# interface-board.net
KiCad netlist of a schematic drawn in Altium Designer
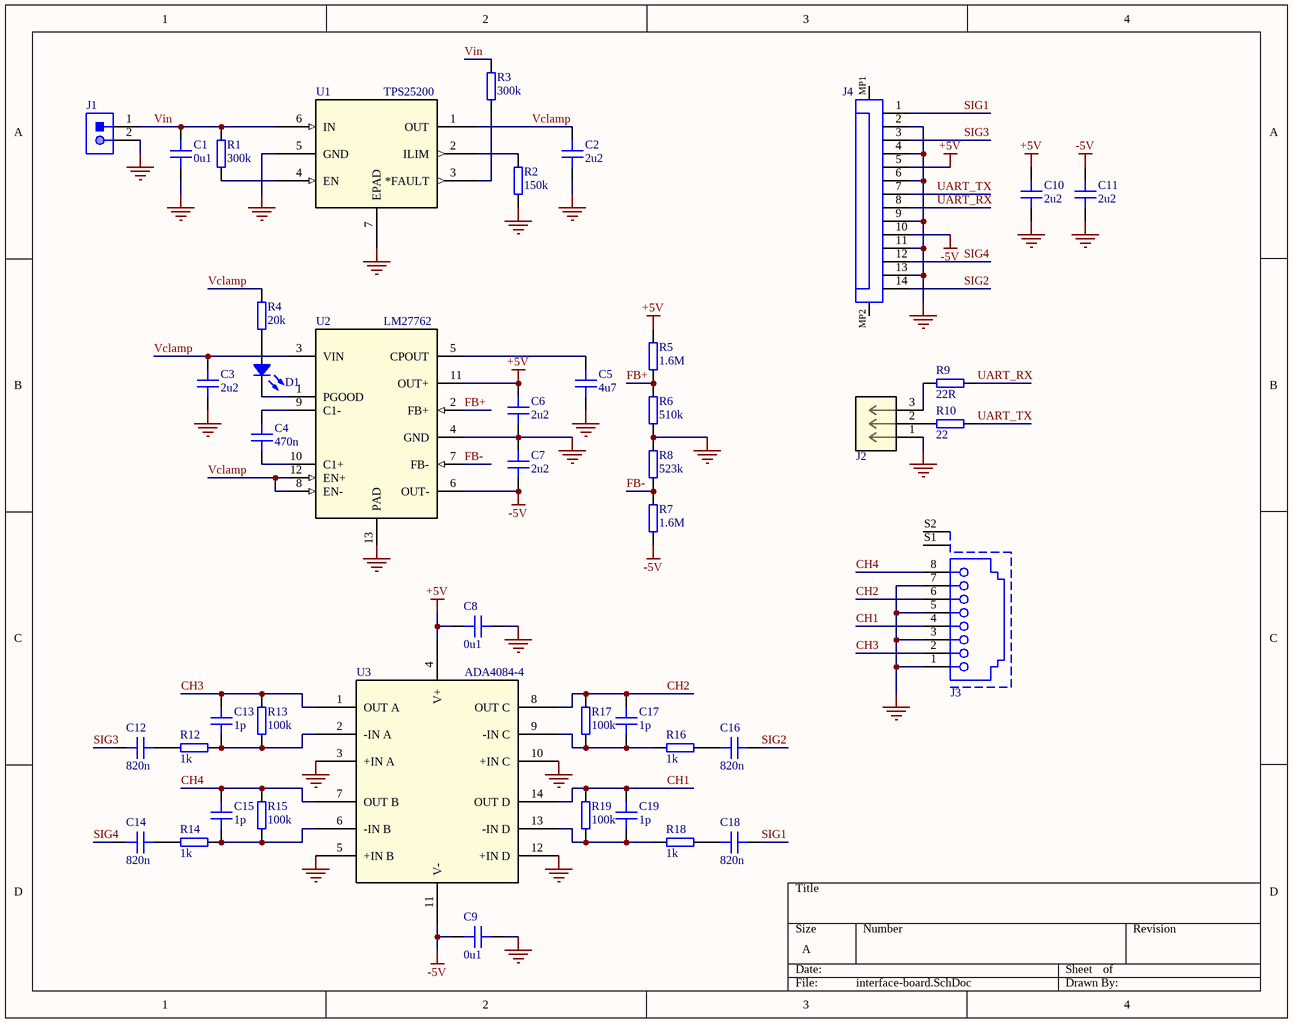
[diagram p0: interface-board.SchDoc]

(export (version "E")
  (design (tool "Eeschema 10.0.6"))
  (components
    (comp (ref "C1")
      (value "0u1")
      (footprint "CAP_0402")
      (description "Capacitor SMD 0402")
      (fields (field (name "VOLTAGE") "50V"))
      (libsource (lib "symbols") (part "CAP_0402"))
    )
    (comp (ref "C2")
      (value "2u2")
      (footprint "CAP_0402")
      (description "Capacitor SMD 0402")
      (fields (field (name "VOLTAGE") "50V"))
      (libsource (lib "symbols") (part "CAP_0402"))
    )
    (comp (ref "C3")
      (value "2u2")
      (footprint "CAP_0402")
      (description "Capacitor SMD 0402")
      (fields (field (name "VOLTAGE") "50V"))
      (libsource (lib "symbols") (part "CAP_0402"))
    )
    (comp (ref "C4")
      (value "470n")
      (footprint "CAP_0402")
      (description "Capacitor SMD 0402")
      (fields (field (name "VOLTAGE") "50V"))
      (libsource (lib "symbols") (part "CAP_0402"))
    )
    (comp (ref "C5")
      (value "4u7")
      (footprint "CAP_0402")
      (description "Capacitor SMD 0402")
      (fields (field (name "VOLTAGE") "50V"))
      (libsource (lib "symbols") (part "CAP_0402"))
    )
    (comp (ref "C6")
      (value "2u2")
      (footprint "CAP_0402")
      (description "Capacitor SMD 0402")
      (fields (field (name "VOLTAGE") "50V"))
      (libsource (lib "symbols") (part "CAP_0402"))
    )
    (comp (ref "C7")
      (value "2u2")
      (footprint "CAP_0402")
      (description "Capacitor SMD 0402")
      (fields (field (name "VOLTAGE") "50V"))
      (libsource (lib "symbols") (part "CAP_0402"))
    )
    (comp (ref "C8")
      (value "0u1")
      (footprint "CAP_0402")
      (description "Capacitor SMD 0402")
      (fields (field (name "VOLTAGE") "50V"))
      (libsource (lib "symbols") (part "CAP_0402"))
    )
    (comp (ref "C9")
      (value "0u1")
      (footprint "CAP_0402")
      (description "Capacitor SMD 0402")
      (fields (field (name "VOLTAGE") "50V"))
      (libsource (lib "symbols") (part "CAP_0402"))
    )
    (comp (ref "C10")
      (value "2u2")
      (footprint "CAP_0402")
      (description "Capacitor SMD 0402")
      (fields (field (name "VOLTAGE") "50V"))
      (libsource (lib "symbols") (part "CAP_0402"))
    )
    (comp (ref "C11")
      (value "2u2")
      (footprint "CAP_0402")
      (description "Capacitor SMD 0402")
      (fields (field (name "VOLTAGE") "50V"))
      (libsource (lib "symbols") (part "CAP_0402"))
    )
    (comp (ref "C12")
      (value "820n")
      (footprint "CAP_0402")
      (description "Capacitor SMD 0402")
      (fields (field (name "VOLTAGE") "50V"))
      (libsource (lib "symbols") (part "CAP_0402"))
    )
    (comp (ref "C13")
      (value "1p")
      (footprint "CAP_0402")
      (description "Capacitor SMD 0402")
      (fields (field (name "VOLTAGE") "50V"))
      (libsource (lib "symbols") (part "CAP_0402"))
    )
    (comp (ref "C14")
      (value "820n")
      (footprint "CAP_0402")
      (description "Capacitor SMD 0402")
      (fields (field (name "VOLTAGE") "50V"))
      (libsource (lib "symbols") (part "CAP_0402"))
    )
    (comp (ref "C15")
      (value "1p")
      (footprint "CAP_0402")
      (description "Capacitor SMD 0402")
      (fields (field (name "VOLTAGE") "50V"))
      (libsource (lib "symbols") (part "CAP_0402"))
    )
    (comp (ref "C16")
      (value "820n")
      (footprint "CAP_0402")
      (description "Capacitor SMD 0402")
      (fields (field (name "VOLTAGE") "50V"))
      (libsource (lib "symbols") (part "CAP_0402"))
    )
    (comp (ref "C17")
      (value "1p")
      (footprint "CAP_0402")
      (description "Capacitor SMD 0402")
      (fields (field (name "VOLTAGE") "50V"))
      (libsource (lib "symbols") (part "CAP_0402"))
    )
    (comp (ref "C18")
      (value "820n")
      (footprint "CAP_0402")
      (description "Capacitor SMD 0402")
      (fields (field (name "VOLTAGE") "50V"))
      (libsource (lib "symbols") (part "CAP_0402"))
    )
    (comp (ref "C19")
      (value "1p")
      (footprint "CAP_0402")
      (description "Capacitor SMD 0402")
      (fields (field (name "VOLTAGE") "50V"))
      (libsource (lib "symbols") (part "CAP_0402"))
    )
    (comp (ref "D1")
      (value "LED_0402")
      (footprint "LED_0402")
      (description "LED SMD 0402")
      (libsource (lib "symbols") (part "LED_0402"))
    )
    (comp (ref "J1")
      (value "XH_2.54_2P")
      (footprint "XH_2.54_2P")
      (description "XH, pitch 2.54 mm, 2 pisition")
      (libsource (lib "symbols") (part "XH_2.54_2P"))
    )
    (comp (ref "J2")
      (value "PH_2.0_3P")
      (footprint "PH_2.0_3P")
      (description "PH, pitch 2.0 mm, 3 pisition")
      (libsource (lib "symbols") (part "PH_2.0_3P"))
    )
    (comp (ref "J3") (value "RJ45") (footprint "RJ45") (libsource (lib "symbols") (part "RJ45")))
    (comp (ref "J4")
      (value "FPC_0.5_14P")
      (footprint "FPC_0.5_14P")
      (description "FPC, Horizontal, pitch 0.5 mm, 14 pins")
      (libsource (lib "symbols") (part "FPC_0.5_14P"))
    )
    (comp (ref "R1")
      (value "300k")
      (footprint "RES_0402")
      (description "Resistor SMD 0402")
      (libsource (lib "symbols") (part "RES_0402"))
    )
    (comp (ref "R2")
      (value "150k")
      (footprint "RES_0402")
      (description "Resistor SMD 0402")
      (libsource (lib "symbols") (part "RES_0402"))
    )
    (comp (ref "R3")
      (value "300k")
      (footprint "RES_0402")
      (description "Resistor SMD 0402")
      (libsource (lib "symbols") (part "RES_0402"))
    )
    (comp (ref "R4")
      (value "20k")
      (footprint "RES_0402")
      (description "Resistor SMD 0402")
      (libsource (lib "symbols") (part "RES_0402"))
    )
    (comp (ref "R5")
      (value "1.6M")
      (footprint "RES_0402")
      (description "Resistor SMD 0402")
      (libsource (lib "symbols") (part "RES_0402"))
    )
    (comp (ref "R6")
      (value "510k")
      (footprint "RES_0402")
      (description "Resistor SMD 0402")
      (libsource (lib "symbols") (part "RES_0402"))
    )
    (comp (ref "R7")
      (value "1.6M")
      (footprint "RES_0402")
      (description "Resistor SMD 0402")
      (libsource (lib "symbols") (part "RES_0402"))
    )
    (comp (ref "R8")
      (value "523k")
      (footprint "RES_0402")
      (description "Resistor SMD 0402")
      (libsource (lib "symbols") (part "RES_0402"))
    )
    (comp (ref "R9")
      (value "22R")
      (footprint "RES_0402")
      (description "Resistor SMD 0402")
      (libsource (lib "symbols") (part "RES_0402"))
    )
    (comp (ref "R10")
      (value "22")
      (footprint "RES_0402")
      (description "Resistor SMD 0402")
      (libsource (lib "symbols") (part "RES_0402"))
    )
    (comp (ref "R12")
      (value "1k")
      (footprint "RES_0402")
      (description "Resistor SMD 0402")
      (libsource (lib "symbols") (part "RES_0402"))
    )
    (comp (ref "R13")
      (value "100k")
      (footprint "RES_0402")
      (description "Resistor SMD 0402")
      (libsource (lib "symbols") (part "RES_0402"))
    )
    (comp (ref "R14")
      (value "1k")
      (footprint "RES_0402")
      (description "Resistor SMD 0402")
      (libsource (lib "symbols") (part "RES_0402"))
    )
    (comp (ref "R15")
      (value "100k")
      (footprint "RES_0402")
      (description "Resistor SMD 0402")
      (libsource (lib "symbols") (part "RES_0402"))
    )
    (comp (ref "R16")
      (value "1k")
      (footprint "RES_0402")
      (description "Resistor SMD 0402")
      (libsource (lib "symbols") (part "RES_0402"))
    )
    (comp (ref "R17")
      (value "100k")
      (footprint "RES_0402")
      (description "Resistor SMD 0402")
      (libsource (lib "symbols") (part "RES_0402"))
    )
    (comp (ref "R18")
      (value "1k")
      (footprint "RES_0402")
      (description "Resistor SMD 0402")
      (libsource (lib "symbols") (part "RES_0402"))
    )
    (comp (ref "R19")
      (value "100k")
      (footprint "RES_0402")
      (description "Resistor SMD 0402")
      (libsource (lib "symbols") (part "RES_0402"))
    )
    (comp (ref "U1")
      (value "TPS25200")
      (footprint "TPS25200")
      (description "5-V eFuse With Precision Adjustable Current Limit and Overvoltage Clamp")
      (fields
        (field (name "MANUFACTURER_PART_NUMBER") "TPS25200DRVR")
        (field (name "COPYRIGHT") "Copyright (C) 2023 Ultra Librarian. All rights reserved.")
      )
      (libsource (lib "symbols") (part "TPS25200"))
    )
    (comp (ref "U2")
      (value "LM27762")
      (footprint "LM27762")
      (description "Low-Noise Positive and Negative Output Integrated Charge Pump Plus LDO")
      (fields
        (field (name "MANUFACTURER_PART_NUMBER") "LM27762DSSR")
        (field (name "COPYRIGHT") "Copyright (C) 2023 Ultra Librarian. All rights reserved.")
      )
      (libsource (lib "symbols") (part "LM27762"))
    )
    (comp (ref "U3")
      (value "ADA4084-4")
      (footprint "ADA4084-4")
      (description "30 V, Low Noise, Rail-to-Rail Input/Output,\r\nLow Power Operational Amplifiers")
      (libsource (lib "symbols") (part "ADA4084-4"))
    )
  )
  (nets
    (net (code "1") (name "+5V") (class "Default")
      (node (ref "C10") (pin "1") (pinfunction "1_1") (pintype "passive"))
      (node (ref "C6") (pin "2") (pinfunction "2_2") (pintype "passive"))
      (node (ref "C8") (pin "2") (pinfunction "2_2") (pintype "passive"))
      (node (ref "J4") (pin "5") (pinfunction "5_5") (pintype "passive"))
      (node (ref "R5") (pin "2") (pinfunction "2_2") (pintype "passive"))
      (node (ref "U2") (pin "11") (pinfunction "OUT+_11") (pintype "power_in"))
      (node (ref "U3") (pin "4") (pinfunction "V+_4") (pintype "passive"))
    )
    (net (code "2") (name "-5V") (class "Default")
      (node (ref "C11") (pin "1") (pinfunction "1_1") (pintype "passive"))
      (node (ref "C7") (pin "1") (pinfunction "1_1") (pintype "passive"))
      (node (ref "C9") (pin "2") (pinfunction "2_2") (pintype "passive"))
      (node (ref "J4") (pin "10") (pinfunction "10_10") (pintype "passive"))
      (node (ref "R7") (pin "1") (pinfunction "1_1") (pintype "passive"))
      (node (ref "U2") (pin "6") (pinfunction "OUT-_6") (pintype "power_in"))
      (node (ref "U3") (pin "11") (pinfunction "V-_11") (pintype "passive"))
    )
    (net (code "3") (name "/CH1") (class "Default")
      (node (ref "C19") (pin "1") (pinfunction "1_1") (pintype "passive"))
      (node (ref "J3") (pin "4") (pinfunction "4_4") (pintype "passive"))
      (node (ref "R19") (pin "1") (pinfunction "1_1") (pintype "passive"))
      (node (ref "U3") (pin "14") (pinfunction "OUT_D_14") (pintype "passive"))
    )
    (net (code "4") (name "/CH2") (class "Default")
      (node (ref "C17") (pin "1") (pinfunction "1_1") (pintype "passive"))
      (node (ref "J3") (pin "6") (pinfunction "6_6") (pintype "passive"))
      (node (ref "R17") (pin "1") (pinfunction "1_1") (pintype "passive"))
      (node (ref "U3") (pin "8") (pinfunction "OUT_C_8") (pintype "passive"))
    )
    (net (code "5") (name "/CH3") (class "Default")
      (node (ref "C13") (pin "1") (pinfunction "1_1") (pintype "passive"))
      (node (ref "J3") (pin "2") (pinfunction "2_2") (pintype "passive"))
      (node (ref "R13") (pin "1") (pinfunction "1_1") (pintype "passive"))
      (node (ref "U3") (pin "1") (pinfunction "OUT_A_1") (pintype "passive"))
    )
    (net (code "6") (name "/CH4") (class "Default")
      (node (ref "C15") (pin "1") (pinfunction "1_1") (pintype "passive"))
      (node (ref "J3") (pin "8") (pinfunction "8_8") (pintype "passive"))
      (node (ref "R15") (pin "1") (pinfunction "1_1") (pintype "passive"))
      (node (ref "U3") (pin "7") (pinfunction "OUT_B_7") (pintype "passive"))
    )
    (net (code "7") (name "/FB+") (class "Default")
      (node (ref "R5") (pin "1") (pinfunction "1_1") (pintype "passive"))
      (node (ref "R6") (pin "2") (pinfunction "2_2") (pintype "passive"))
      (node (ref "U2") (pin "2") (pinfunction "FB+_2") (pintype "input"))
    )
    (net (code "8") (name "/FB-") (class "Default")
      (node (ref "R7") (pin "2") (pinfunction "2_2") (pintype "passive"))
      (node (ref "R8") (pin "1") (pinfunction "1_1") (pintype "passive"))
      (node (ref "U2") (pin "7") (pinfunction "FB-_7") (pintype "input"))
    )
    (net (code "9") (name "/SIG1") (class "Default")
      (node (ref "C18") (pin "1") (pinfunction "1_1") (pintype "passive"))
      (node (ref "J4") (pin "1") (pinfunction "1_1") (pintype "passive"))
    )
    (net (code "10") (name "/SIG2") (class "Default")
      (node (ref "C16") (pin "1") (pinfunction "1_1") (pintype "passive"))
      (node (ref "J4") (pin "14") (pinfunction "14_14") (pintype "passive"))
    )
    (net (code "11") (name "/SIG3") (class "Default")
      (node (ref "C12") (pin "1") (pinfunction "1_1") (pintype "passive"))
      (node (ref "J4") (pin "3") (pinfunction "3_3") (pintype "passive"))
    )
    (net (code "12") (name "/SIG4") (class "Default")
      (node (ref "C14") (pin "1") (pinfunction "1_1") (pintype "passive"))
      (node (ref "J4") (pin "12") (pinfunction "12_12") (pintype "passive"))
    )
    (net (code "13") (name "/UART_RX") (class "Default")
      (node (ref "J4") (pin "8") (pinfunction "8_8") (pintype "passive"))
      (node (ref "R9") (pin "1") (pinfunction "1_1") (pintype "passive"))
    )
    (net (code "14") (name "/UART_TX") (class "Default")
      (node (ref "J4") (pin "7") (pinfunction "7_7") (pintype "passive"))
      (node (ref "R10") (pin "1") (pinfunction "1_1") (pintype "passive"))
    )
    (net (code "15") (name "/Vclamp") (class "Default")
      (node (ref "C2") (pin "2") (pinfunction "2_2") (pintype "passive"))
      (node (ref "C3") (pin "2") (pinfunction "2_2") (pintype "passive"))
      (node (ref "R4") (pin "2") (pinfunction "2_2") (pintype "passive"))
      (node (ref "U1") (pin "1") (pinfunction "OUT_1") (pintype "power_in"))
      (node (ref "U2") (pin "12") (pinfunction "EN+_12") (pintype "input"))
      (node (ref "U2") (pin "3") (pinfunction "VIN_3") (pintype "power_in"))
      (node (ref "U2") (pin "8") (pinfunction "EN-_8") (pintype "input"))
    )
    (net (code "16") (name "/Vin") (class "Default")
      (node (ref "C1") (pin "2") (pinfunction "2_2") (pintype "passive"))
      (node (ref "J1") (pin "1") (pinfunction "1_1") (pintype "passive"))
      (node (ref "R1") (pin "2") (pinfunction "2_2") (pintype "passive"))
      (node (ref "R3") (pin "2") (pinfunction "2_2") (pintype "passive"))
      (node (ref "U1") (pin "6") (pinfunction "IN_6") (pintype "input"))
    )
    (net (code "17") (name "GND") (class "Default")
      (node (ref "C1") (pin "1") (pinfunction "1_1") (pintype "passive"))
      (node (ref "C10") (pin "2") (pinfunction "2_2") (pintype "passive"))
      (node (ref "C11") (pin "2") (pinfunction "2_2") (pintype "passive"))
      (node (ref "C2") (pin "1") (pinfunction "1_1") (pintype "passive"))
      (node (ref "C3") (pin "1") (pinfunction "1_1") (pintype "passive"))
      (node (ref "C5") (pin "1") (pinfunction "1_1") (pintype "passive"))
      (node (ref "C6") (pin "1") (pinfunction "1_1") (pintype "passive"))
      (node (ref "C7") (pin "2") (pinfunction "2_2") (pintype "passive"))
      (node (ref "C8") (pin "1") (pinfunction "1_1") (pintype "passive"))
      (node (ref "C9") (pin "1") (pinfunction "1_1") (pintype "passive"))
      (node (ref "J1") (pin "2") (pinfunction "2_2") (pintype "passive"))
      (node (ref "J2") (pin "1") (pinfunction "1_1") (pintype "passive"))
      (node (ref "J3") (pin "1") (pinfunction "1_1") (pintype "passive"))
      (node (ref "J3") (pin "3") (pinfunction "3_3") (pintype "passive"))
      (node (ref "J3") (pin "5") (pinfunction "5_5") (pintype "passive"))
      (node (ref "J3") (pin "7") (pinfunction "7_7") (pintype "passive"))
      (node (ref "J4") (pin "11") (pinfunction "11_11") (pintype "passive"))
      (node (ref "J4") (pin "13") (pinfunction "13_13") (pintype "passive"))
      (node (ref "J4") (pin "2") (pinfunction "2_2") (pintype "passive"))
      (node (ref "J4") (pin "4") (pinfunction "4_4") (pintype "passive"))
      (node (ref "J4") (pin "6") (pinfunction "6_6") (pintype "passive"))
      (node (ref "J4") (pin "9") (pinfunction "9_9") (pintype "passive"))
      (node (ref "R2") (pin "1") (pinfunction "1_1") (pintype "passive"))
      (node (ref "R6") (pin "1") (pinfunction "1_1") (pintype "passive"))
      (node (ref "R8") (pin "2") (pinfunction "2_2") (pintype "passive"))
      (node (ref "U1") (pin "5") (pinfunction "GND_5") (pintype "power_in"))
      (node (ref "U1") (pin "7") (pinfunction "EPAD_7") (pintype "passive"))
      (node (ref "U2") (pin "13") (pinfunction "PAD_13") (pintype "power_in"))
      (node (ref "U2") (pin "4") (pinfunction "GND_4") (pintype "power_in"))
      (node (ref "U3") (pin "10") (pinfunction "+IN_C_10") (pintype "passive"))
      (node (ref "U3") (pin "12") (pinfunction "+IN_D_12") (pintype "passive"))
      (node (ref "U3") (pin "3") (pinfunction "+IN_A_3") (pintype "passive"))
      (node (ref "U3") (pin "5") (pinfunction "+IN_B_5") (pintype "passive"))
    )
    (net (code "18") (name "Net-(C12-Pad2)") (class "Default")
      (node (ref "C12") (pin "2") (pinfunction "2_2") (pintype "passive"))
      (node (ref "R12") (pin "2") (pinfunction "2_2") (pintype "passive"))
    )
    (net (code "19") (name "Net-(C14-Pad2)") (class "Default")
      (node (ref "C14") (pin "2") (pinfunction "2_2") (pintype "passive"))
      (node (ref "R14") (pin "2") (pinfunction "2_2") (pintype "passive"))
    )
    (net (code "20") (name "Net-(C16-Pad2)") (class "Default")
      (node (ref "C16") (pin "2") (pinfunction "2_2") (pintype "passive"))
      (node (ref "R16") (pin "2") (pinfunction "2_2") (pintype "passive"))
    )
    (net (code "21") (name "Net-(C18-Pad2)") (class "Default")
      (node (ref "C18") (pin "2") (pinfunction "2_2") (pintype "passive"))
      (node (ref "R18") (pin "2") (pinfunction "2_2") (pintype "passive"))
    )
    (net (code "22") (name "Net-(D1-PadA)") (class "Default")
      (node (ref "D1") (pin "A") (pinfunction "A_A") (pintype "passive"))
      (node (ref "R4") (pin "1") (pinfunction "1_1") (pintype "passive"))
    )
    (net (code "23") (name "Net-(J2-Pad2)") (class "Default")
      (node (ref "J2") (pin "2") (pinfunction "2_2") (pintype "passive"))
      (node (ref "R10") (pin "2") (pinfunction "2_2") (pintype "passive"))
    )
    (net (code "24") (name "Net-(J2-Pad3)") (class "Default")
      (node (ref "J2") (pin "3") (pinfunction "3_3") (pintype "passive"))
      (node (ref "R9") (pin "2") (pinfunction "2_2") (pintype "passive"))
    )
    (net (code "25") (name "Net-(U1-*FAULT)") (class "Default")
      (node (ref "R3") (pin "1") (pinfunction "1_1") (pintype "passive"))
      (node (ref "U1") (pin "3") (pinfunction "*FAULT_3") (pintype "output"))
    )
    (net (code "26") (name "Net-(U1-EN)") (class "Default")
      (node (ref "R1") (pin "1") (pinfunction "1_1") (pintype "passive"))
      (node (ref "U1") (pin "4") (pinfunction "EN_4") (pintype "input"))
    )
    (net (code "27") (name "Net-(U1-ILIM)") (class "Default")
      (node (ref "R2") (pin "2") (pinfunction "2_2") (pintype "passive"))
      (node (ref "U1") (pin "2") (pinfunction "ILIM_2") (pintype "output"))
    )
    (net (code "28") (name "Net-(U2-C1+)") (class "Default")
      (node (ref "C4") (pin "1") (pinfunction "1_1") (pintype "passive"))
      (node (ref "U2") (pin "10") (pinfunction "C1+_10") (pintype "passive"))
    )
    (net (code "29") (name "Net-(U2-C1-)") (class "Default")
      (node (ref "C4") (pin "2") (pinfunction "2_2") (pintype "passive"))
      (node (ref "U2") (pin "9") (pinfunction "C1-_9") (pintype "passive"))
    )
    (net (code "30") (name "Net-(U2-CPOUT)") (class "Default")
      (node (ref "C5") (pin "2") (pinfunction "2_2") (pintype "passive"))
      (node (ref "U2") (pin "5") (pinfunction "CPOUT_5") (pintype "power_in"))
    )
    (net (code "31") (name "Net-(U2-PGOOD)") (class "Default")
      (node (ref "D1") (pin "K") (pinfunction "K_K") (pintype "passive"))
      (node (ref "U2") (pin "1") (pinfunction "PGOOD_1") (pintype "open_collector"))
    )
    (net (code "32") (name "Net-(U3--IN_A)") (class "Default")
      (node (ref "C13") (pin "2") (pinfunction "2_2") (pintype "passive"))
      (node (ref "R12") (pin "1") (pinfunction "1_1") (pintype "passive"))
      (node (ref "R13") (pin "2") (pinfunction "2_2") (pintype "passive"))
      (node (ref "U3") (pin "2") (pinfunction "-IN_A_2") (pintype "passive"))
    )
    (net (code "33") (name "Net-(U3--IN_B)") (class "Default")
      (node (ref "C15") (pin "2") (pinfunction "2_2") (pintype "passive"))
      (node (ref "R14") (pin "1") (pinfunction "1_1") (pintype "passive"))
      (node (ref "R15") (pin "2") (pinfunction "2_2") (pintype "passive"))
      (node (ref "U3") (pin "6") (pinfunction "-IN_B_6") (pintype "passive"))
    )
    (net (code "34") (name "Net-(U3--IN_C)") (class "Default")
      (node (ref "C17") (pin "2") (pinfunction "2_2") (pintype "passive"))
      (node (ref "R16") (pin "1") (pinfunction "1_1") (pintype "passive"))
      (node (ref "R17") (pin "2") (pinfunction "2_2") (pintype "passive"))
      (node (ref "U3") (pin "9") (pinfunction "-IN_C_9") (pintype "passive"))
    )
    (net (code "35") (name "Net-(U3--IN_D)") (class "Default")
      (node (ref "C19") (pin "2") (pinfunction "2_2") (pintype "passive"))
      (node (ref "R18") (pin "1") (pinfunction "1_1") (pintype "passive"))
      (node (ref "R19") (pin "2") (pinfunction "2_2") (pintype "passive"))
      (node (ref "U3") (pin "13") (pinfunction "-IN_D_13") (pintype "passive"))
    )
    (net (code "36") (name "unconnected-(J3-PadS1)") (class "Default")
      (node (ref "J3") (pin "S1") (pinfunction "S1_S1") (pintype "passive"))
    )
    (net (code "37") (name "unconnected-(J3-PadS2)") (class "Default")
      (node (ref "J3") (pin "S2") (pinfunction "S2_S2") (pintype "passive"))
    )
    (net (code "38") (name "unconnected-(J4-PadMP1)") (class "Default")
      (node (ref "J4") (pin "MP1") (pinfunction "MP1_MP1") (pintype "passive"))
    )
    (net (code "39") (name "unconnected-(J4-PadMP2)") (class "Default")
      (node (ref "J4") (pin "MP2") (pinfunction "MP2_MP2") (pintype "passive"))
    )
  )
)
